# Adafruit-Feather.net
KiCad netlist of a schematic drawn in EAGLE
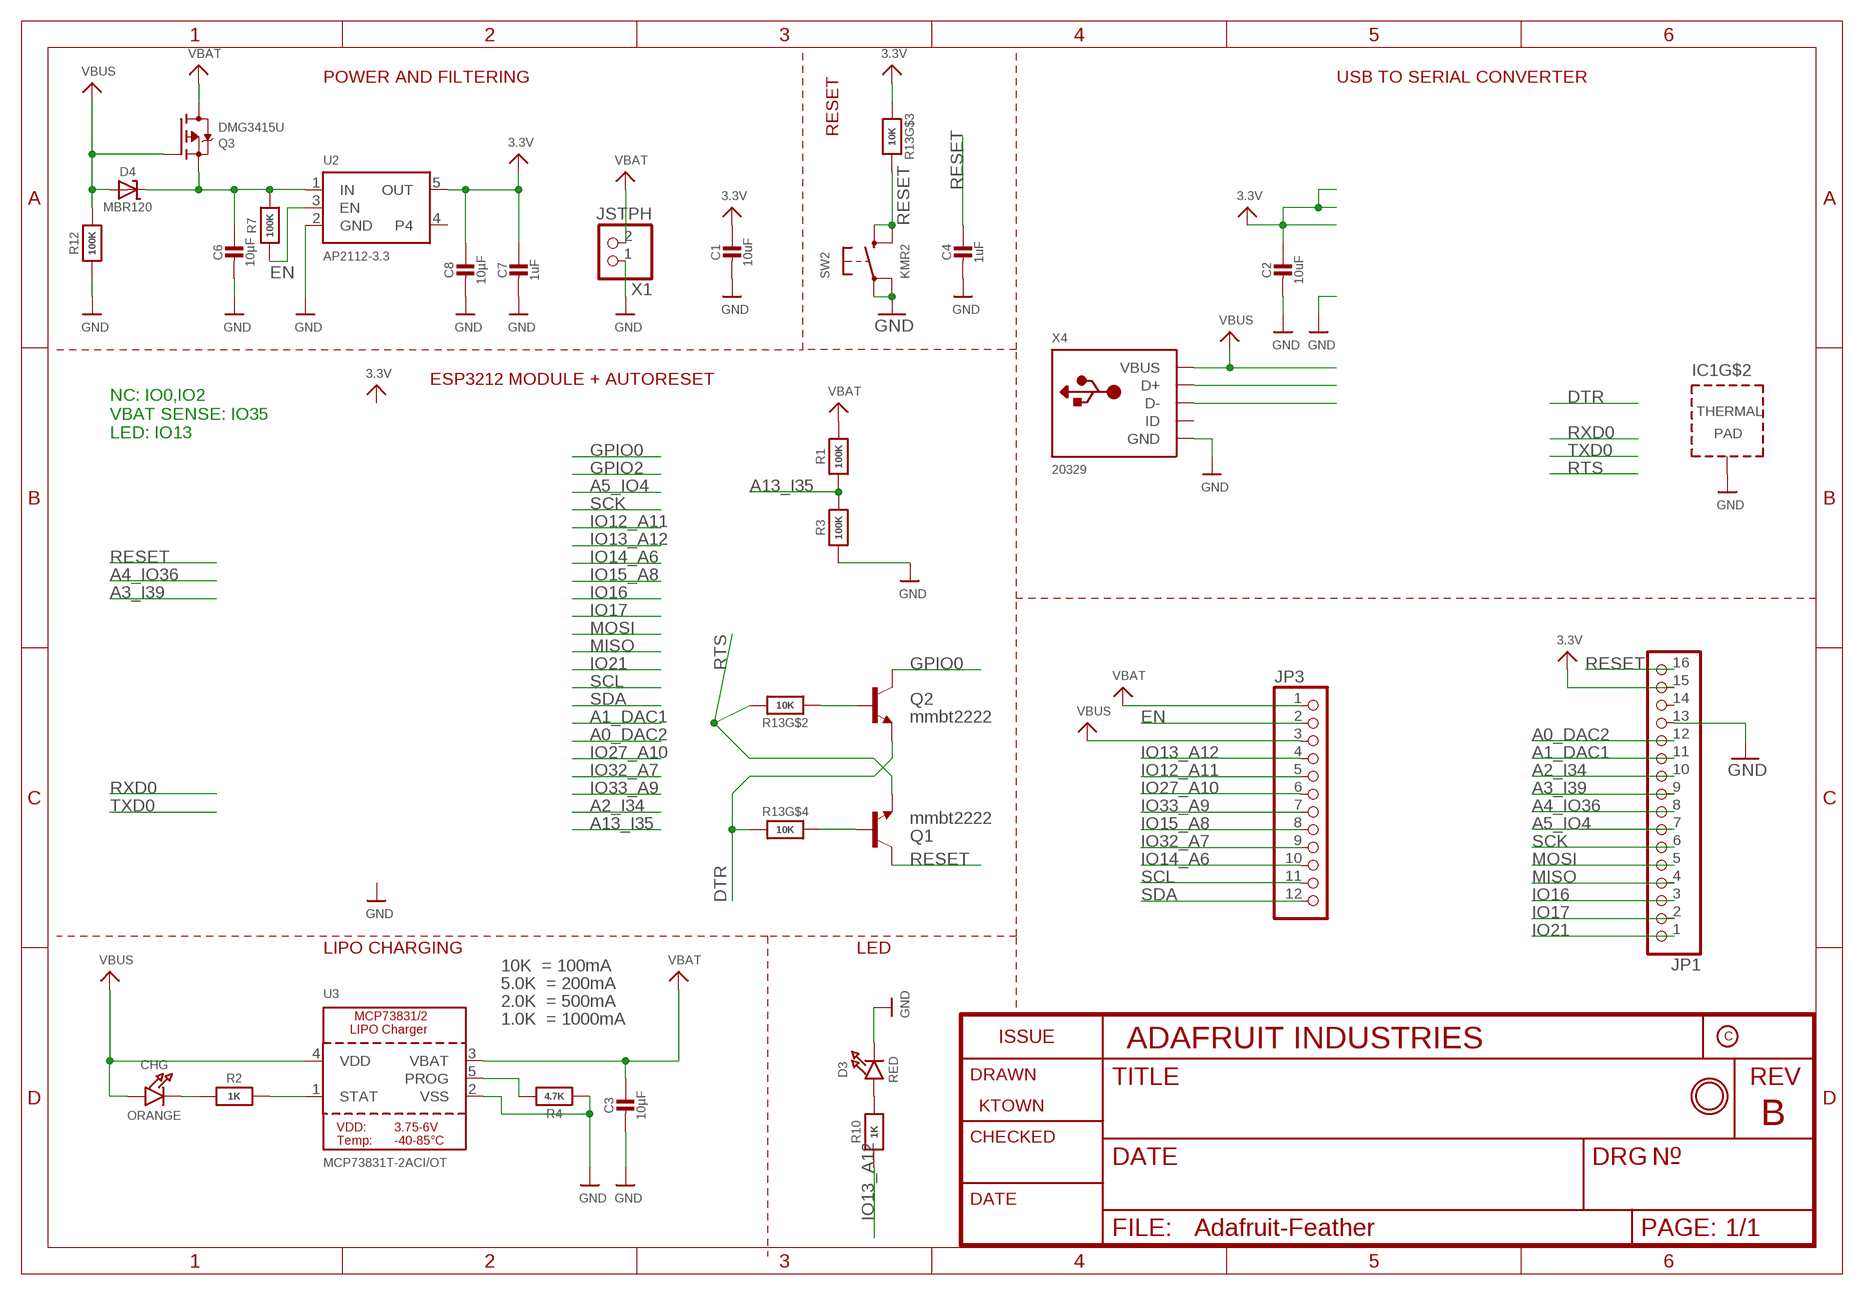
[diagram p0: schematic, sheet 1]

(export (version "E")
  (design (tool "Eeschema 10.0.6"))
  (components
    (comp (ref "C1")
      (value "10uF")
      (footprint "eagle-import:0805-NO")
      (libsource (lib "eagle-import") (part "CAP_CERAMIC0805-NOOUTLINE"))
    )
    (comp (ref "C2")
      (value "10uF")
      (footprint "eagle-import:0805-NO")
      (libsource (lib "eagle-import") (part "CAP_CERAMIC0805-NOOUTLINE"))
    )
    (comp (ref "C3")
      (value "10µF")
      (footprint "eagle-import:0805-NO")
      (libsource (lib "eagle-import") (part "CAP_CERAMIC0805-NOOUTLINE"))
    )
    (comp (ref "C4")
      (value "1uF")
      (footprint "eagle-import:0603-NO")
      (libsource (lib "eagle-import") (part "CAP_CERAMIC0603_NO"))
    )
    (comp (ref "C6")
      (value "10µF")
      (footprint "eagle-import:0805-NO")
      (libsource (lib "eagle-import") (part "CAP_CERAMIC0805-NOOUTLINE"))
    )
    (comp (ref "C7")
      (value "1uF")
      (footprint "eagle-import:0603-NO")
      (libsource (lib "eagle-import") (part "CAP_CERAMIC0603_NO"))
    )
    (comp (ref "C8")
      (value "10µF")
      (footprint "eagle-import:0805-NO")
      (libsource (lib "eagle-import") (part "CAP_CERAMIC0805-NOOUTLINE"))
    )
    (comp (ref "CHG")
      (value "ORANGE")
      (footprint "eagle-import:CHIPLED_0805_NOOUTLINE")
      (libsource (lib "eagle-import") (part "LED0805_NOOUTLINE"))
    )
    (comp (ref "D3")
      (value "RED")
      (footprint "eagle-import:CHIPLED_0805_NOOUTLINE")
      (libsource (lib "eagle-import") (part "LED0805_NOOUTLINE"))
    )
    (comp (ref "D4")
      (value "MBR120")
      (footprint "eagle-import:SOD-123")
      (libsource (lib "eagle-import") (part "DIODE-SCHOTTKYSOD-123"))
    )
    (comp (ref "IC1")
      (value "CP2104")
      (footprint "eagle-import:QFN24_4MM_SMSC")
      (libsource (lib "eagle-import") (part "CP2104"))
    )
    (comp (ref "JP1")
      (value "HEADER-1X16_MIN")
      (footprint "eagle-import:1X16_ROUND_MIN")
      (libsource (lib "eagle-import") (part "HEADER-1X16_MIN"))
    )
    (comp (ref "JP3")
      (value "HEADER-1X12_MIN")
      (footprint "eagle-import:1X12_ROUND_MIN")
      (libsource (lib "eagle-import") (part "HEADER-1X12_MIN"))
    )
    (comp (ref "Q1")
      (value "mmbt2222")
      (footprint "eagle-import:SOT23-3")
      (libsource (lib "eagle-import") (part "TRANSISTOR_NPNSOT23-3"))
    )
    (comp (ref "Q2")
      (value "mmbt2222")
      (footprint "eagle-import:SOT23-3")
      (libsource (lib "eagle-import") (part "TRANSISTOR_NPNSOT23-3"))
    )
    (comp (ref "Q3")
      (value "DMG3415U")
      (footprint "eagle-import:SOT23-R")
      (libsource (lib "eagle-import") (part "MOSFET-P"))
    )
    (comp (ref "R1")
      (value "100K")
      (footprint "eagle-import:0603-NO")
      (libsource (lib "eagle-import") (part "RESISTOR_0603_NOOUT"))
    )
    (comp (ref "R2")
      (value "1K")
      (footprint "eagle-import:0603-NO")
      (libsource (lib "eagle-import") (part "RESISTOR_0603_NOOUT"))
    )
    (comp (ref "R3")
      (value "100K")
      (footprint "eagle-import:0603-NO")
      (libsource (lib "eagle-import") (part "RESISTOR_0603_NOOUT"))
    )
    (comp (ref "R4")
      (value "4.7K")
      (footprint "eagle-import:0603-NO")
      (libsource (lib "eagle-import") (part "RESISTOR_0603_NOOUT"))
    )
    (comp (ref "R7")
      (value "100K")
      (footprint "eagle-import:0603-NO")
      (libsource (lib "eagle-import") (part "RESISTOR_0603_NOOUT"))
    )
    (comp (ref "R10")
      (value "1K")
      (footprint "eagle-import:0603-NO")
      (libsource (lib "eagle-import") (part "RESISTOR_0603_NOOUT"))
    )
    (comp (ref "R12")
      (value "100K")
      (footprint "eagle-import:0603-NO")
      (libsource (lib "eagle-import") (part "RESISTOR_0603_NOOUT"))
    )
    (comp (ref "R13")
      (value "10K")
      (footprint "eagle-import:RESPACK_4X0603")
      (libsource (lib "eagle-import") (part "RESISTOR_4PACK"))
    )
    (comp (ref "SW2")
      (value "KMR2")
      (footprint "eagle-import:BTN_KMR2_4.6X2.8")
      (libsource (lib "eagle-import") (part "SWITCH_TACT_SMT4.6X2.8"))
    )
    (comp (ref "U$32")
      (value "MOUNTINGHOLE2.5")
      (footprint "eagle-import:MOUNTINGHOLE_2.5_PLATED")
      (libsource (lib "eagle-import") (part "MOUNTINGHOLE2.5"))
    )
    (comp (ref "U2")
      (value "AP2112-3.3")
      (footprint "eagle-import:SOT23-5")
      (libsource (lib "eagle-import") (part "VREG_SOT23-5"))
    )
    (comp (ref "U3")
      (value "MCP73831T-2ACI/OT")
      (footprint "eagle-import:SOT23-5")
      (libsource (lib "eagle-import") (part "MCP73831/2"))
    )
    (comp (ref "X1")
      (value "JSTPH")
      (footprint "eagle-import:JSTPH2")
      (libsource (lib "eagle-import") (part "CON_JST_PH_2PIN"))
    )
    (comp (ref "X4")
      (value "20329")
      (footprint "eagle-import:4UCONN_20329_V2")
      (libsource (lib "eagle-import") (part "USB_MICRO_20329_V2"))
    )
  )
  (nets
    (net (code "1") (name "/A0_DAC2") (class "Default")
      (node (ref "JP1") (pin "12") (pinfunction "12_12") (pintype "passive"))
    )
    (net (code "2") (name "/A1_DAC1") (class "Default")
      (node (ref "JP1") (pin "11") (pinfunction "11_11") (pintype "passive"))
    )
    (net (code "3") (name "/A2_I34") (class "Default")
      (node (ref "JP1") (pin "10") (pinfunction "10_10") (pintype "passive"))
    )
    (net (code "4") (name "/A3_I39") (class "Default")
      (node (ref "JP1") (pin "9") (pinfunction "9_9") (pintype "passive"))
    )
    (net (code "5") (name "/A4_IO36") (class "Default")
      (node (ref "JP1") (pin "8") (pinfunction "8_8") (pintype "passive"))
    )
    (net (code "6") (name "/A5_IO4") (class "Default")
      (node (ref "JP1") (pin "7") (pinfunction "7_7") (pintype "passive"))
    )
    (net (code "7") (name "/A13_I35") (class "Default")
      (node (ref "R1") (pin "1") (pinfunction "1_1") (pintype "passive"))
      (node (ref "R3") (pin "2") (pinfunction "2_2") (pintype "passive"))
    )
    (net (code "8") (name "/DTR") (class "Default")
      (node (ref "Q2") (pin "2") (pinfunction "E_2") (pintype "passive"))
      (node (ref "R13") (pin "4") (pinfunction "1_4") (pintype "passive"))
    )
    (net (code "9") (name "/EN") (class "Default")
      (node (ref "JP3") (pin "2") (pinfunction "2_2") (pintype "passive"))
      (node (ref "R7") (pin "1") (pinfunction "1_1") (pintype "passive"))
      (node (ref "U2") (pin "3") (pinfunction "EN_3") (pintype "input"))
    )
    (net (code "10") (name "/GPIO0") (class "Default")
      (node (ref "Q2") (pin "3") (pinfunction "C_3") (pintype "passive"))
    )
    (net (code "12") (name "/IO12_A11") (class "Default")
      (node (ref "JP3") (pin "5") (pinfunction "5_5") (pintype "passive"))
    )
    (net (code "13") (name "/IO13_A12") (class "Default")
      (node (ref "JP3") (pin "4") (pinfunction "4_4") (pintype "passive"))
      (node (ref "R10") (pin "1") (pinfunction "1_1") (pintype "passive"))
    )
    (net (code "14") (name "/IO14_A6") (class "Default")
      (node (ref "JP3") (pin "10") (pinfunction "10_10") (pintype "passive"))
    )
    (net (code "15") (name "/IO15_A8") (class "Default")
      (node (ref "JP3") (pin "8") (pinfunction "8_8") (pintype "passive"))
    )
    (net (code "16") (name "/IO16") (class "Default")
      (node (ref "JP1") (pin "3") (pinfunction "3_3") (pintype "passive"))
    )
    (net (code "17") (name "/IO17") (class "Default")
      (node (ref "JP1") (pin "2") (pinfunction "2_2") (pintype "passive"))
    )
    (net (code "18") (name "/IO21") (class "Default")
      (node (ref "JP1") (pin "1") (pinfunction "1_1") (pintype "passive"))
    )
    (net (code "19") (name "/IO27_A10") (class "Default")
      (node (ref "JP3") (pin "6") (pinfunction "6_6") (pintype "passive"))
    )
    (net (code "20") (name "/IO32_A7") (class "Default")
      (node (ref "JP3") (pin "9") (pinfunction "9_9") (pintype "passive"))
    )
    (net (code "21") (name "/IO33_A9") (class "Default")
      (node (ref "JP3") (pin "7") (pinfunction "7_7") (pintype "passive"))
    )
    (net (code "22") (name "/MISO") (class "Default")
      (node (ref "JP1") (pin "4") (pinfunction "4_4") (pintype "passive"))
    )
    (net (code "23") (name "/MOSI") (class "Default")
      (node (ref "JP1") (pin "5") (pinfunction "5_5") (pintype "passive"))
    )
    (net (code "24") (name "/RESET") (class "Default")
      (node (ref "C4") (pin "1") (pinfunction "1_1") (pintype "passive"))
      (node (ref "JP1") (pin "16") (pinfunction "16_16") (pintype "passive"))
      (node (ref "Q1") (pin "3") (pinfunction "C_3") (pintype "passive"))
      (node (ref "R13") (pin "6") (pinfunction "2_6") (pintype "passive"))
      (node (ref "SW2") (pin "B") (pinfunction "S_B") (pintype "passive"))
      (node (ref "SW2") (pin "B'") (pinfunction "S1_B'") (pintype "passive"))
    )
    (net (code "25") (name "/RTS") (class "Default")
      (node (ref "Q1") (pin "2") (pinfunction "E_2") (pintype "passive"))
      (node (ref "R13") (pin "7") (pinfunction "2_7") (pintype "passive"))
    )
    (net (code "27") (name "/SCK") (class "Default")
      (node (ref "JP1") (pin "6") (pinfunction "6_6") (pintype "passive"))
    )
    (net (code "28") (name "/SCL") (class "Default")
      (node (ref "JP3") (pin "11") (pinfunction "11_11") (pintype "passive"))
    )
    (net (code "29") (name "/SDA") (class "Default")
      (node (ref "JP3") (pin "12") (pinfunction "12_12") (pintype "passive"))
    )
    (net (code "31") (name "3.3V") (class "Default")
      (node (ref "C1") (pin "1") (pinfunction "1_1") (pintype "passive"))
      (node (ref "C2") (pin "1") (pinfunction "1_1") (pintype "passive"))
      (node (ref "C7") (pin "1") (pinfunction "1_1") (pintype "passive"))
      (node (ref "C8") (pin "1") (pinfunction "1_1") (pintype "passive"))
      (node (ref "JP1") (pin "15") (pinfunction "15_15") (pintype "passive"))
      (node (ref "R13") (pin "3") (pinfunction "1_3") (pintype "passive"))
      (node (ref "U2") (pin "5") (pinfunction "OUT_5") (pintype "power_in"))
    )
    (net (code "32") (name "GND") (class "Default")
      (node (ref "C1") (pin "2") (pinfunction "2_2") (pintype "passive"))
      (node (ref "C2") (pin "2") (pinfunction "2_2") (pintype "passive"))
      (node (ref "C3") (pin "2") (pinfunction "2_2") (pintype "passive"))
      (node (ref "C4") (pin "2") (pinfunction "2_2") (pintype "passive"))
      (node (ref "C6") (pin "2") (pinfunction "2_2") (pintype "passive"))
      (node (ref "C7") (pin "2") (pinfunction "2_2") (pintype "passive"))
      (node (ref "C8") (pin "2") (pinfunction "2_2") (pintype "passive"))
      (node (ref "D3") (pin "C") (pinfunction "C_C") (pintype "passive"))
      (node (ref "IC1") (pin "THERM") (pinfunction "TP_THERM") (pintype "power_in"))
      (node (ref "JP1") (pin "13") (pinfunction "13_13") (pintype "passive"))
      (node (ref "R12") (pin "1") (pinfunction "1_1") (pintype "passive"))
      (node (ref "R3") (pin "1") (pinfunction "1_1") (pintype "passive"))
      (node (ref "R4") (pin "1") (pinfunction "1_1") (pintype "passive"))
      (node (ref "SW2") (pin "A") (pinfunction "P_A") (pintype "passive"))
      (node (ref "SW2") (pin "A'") (pinfunction "P1_A'") (pintype "passive"))
      (node (ref "U2") (pin "2") (pinfunction "GND_2") (pintype "power_in"))
      (node (ref "U3") (pin "2") (pinfunction "VSS_2") (pintype "power_in"))
      (node (ref "X1") (pin "1") (pinfunction "1_1") (pintype "passive"))
      (node (ref "X4") (pin "BASE@1") (pinfunction "GND_BASE@1") (pintype "power_in"))
      (node (ref "X4") (pin "BASE@2") (pinfunction "GND_BASE@2") (pintype "power_in"))
      (node (ref "X4") (pin "GND") (pinfunction "GND_GND") (pintype "power_in"))
      (node (ref "X4") (pin "SPRT@1") (pinfunction "GND_SPRT@1") (pintype "power_in"))
      (node (ref "X4") (pin "SPRT@2") (pinfunction "GND_SPRT@2") (pintype "power_in"))
      (node (ref "X4") (pin "SPRT@3") (pinfunction "GND_SPRT@3") (pintype "power_in"))
      (node (ref "X4") (pin "SPRT@4") (pinfunction "GND_SPRT@4") (pintype "power_in"))
    )
    (net (code "33") (name "Net-(CHG-PadC)") (class "Default")
      (node (ref "CHG") (pin "C") (pinfunction "C_C") (pintype "passive"))
      (node (ref "R2") (pin "1") (pinfunction "1_1") (pintype "passive"))
    )
    (net (code "34") (name "Net-(D3-PadA)") (class "Default")
      (node (ref "D3") (pin "A") (pinfunction "A_A") (pintype "passive"))
      (node (ref "R10") (pin "2") (pinfunction "2_2") (pintype "passive"))
    )
    (net (code "35") (name "Net-(Q1-B)") (class "Default")
      (node (ref "Q1") (pin "1") (pinfunction "B_1") (pintype "passive"))
      (node (ref "R13") (pin "5") (pinfunction "2_5") (pintype "passive"))
    )
    (net (code "36") (name "Net-(Q2-B)") (class "Default")
      (node (ref "Q2") (pin "1") (pinfunction "B_1") (pintype "passive"))
      (node (ref "R13") (pin "2") (pinfunction "1_2") (pintype "passive"))
    )
    (net (code "37") (name "Net-(Q3-S)") (class "Default")
      (node (ref "C6") (pin "1") (pinfunction "1_1") (pintype "passive"))
      (node (ref "D4") (pin "C") (pinfunction "C_C") (pintype "passive"))
      (node (ref "Q3") (pin "2") (pinfunction "S_2") (pintype "passive"))
      (node (ref "R7") (pin "2") (pinfunction "2_2") (pintype "passive"))
      (node (ref "U2") (pin "1") (pinfunction "IN_1") (pintype "power_in"))
    )
    (net (code "38") (name "Net-(U3-PROG)") (class "Default")
      (node (ref "R4") (pin "2") (pinfunction "2_2") (pintype "passive"))
      (node (ref "U3") (pin "5") (pinfunction "PROG_5") (pintype "input"))
    )
    (net (code "39") (name "Net-(U3-STAT)") (class "Default")
      (node (ref "R2") (pin "2") (pinfunction "2_2") (pintype "passive"))
      (node (ref "U3") (pin "1") (pinfunction "STAT_1") (pintype "output"))
    )
    (net (code "40") (name "VBAT") (class "Default")
      (node (ref "C3") (pin "1") (pinfunction "1_1") (pintype "passive"))
      (node (ref "JP3") (pin "1") (pinfunction "1_1") (pintype "passive"))
      (node (ref "Q3") (pin "3") (pinfunction "D_3") (pintype "passive"))
      (node (ref "R1") (pin "2") (pinfunction "2_2") (pintype "passive"))
      (node (ref "U3") (pin "3") (pinfunction "VBAT_3") (pintype "power_in"))
      (node (ref "X1") (pin "2") (pinfunction "2_2") (pintype "passive"))
    )
    (net (code "41") (name "VBUS") (class "Default")
      (node (ref "CHG") (pin "A") (pinfunction "A_A") (pintype "passive"))
      (node (ref "D4") (pin "A") (pinfunction "A_A") (pintype "passive"))
      (node (ref "JP3") (pin "3") (pinfunction "3_3") (pintype "passive"))
      (node (ref "Q3") (pin "1") (pinfunction "G_1") (pintype "passive"))
      (node (ref "R12") (pin "2") (pinfunction "2_2") (pintype "passive"))
      (node (ref "U3") (pin "4") (pinfunction "VDD_4") (pintype "power_in"))
      (node (ref "X4") (pin "VBUS") (pinfunction "VBUS_VBUS") (pintype "power_in"))
    )
    (net (code "42") (name "unconnected-(JP1-Pad14)") (class "Default")
      (node (ref "JP1") (pin "14") (pinfunction "14_14") (pintype "passive"))
    )
    (net (code "43") (name "unconnected-(U2-P4-Pad4)") (class "Default")
      (node (ref "U2") (pin "4") (pinfunction "P4_4") (pintype "bidirectional"))
    )
    (net (code "44") (name "unconnected-(X4-PadD+)") (class "Default")
      (node (ref "X4") (pin "D+") (pinfunction "D+_D+") (pintype "bidirectional"))
    )
    (net (code "45") (name "unconnected-(X4-PadD-)") (class "Default")
      (node (ref "X4") (pin "D-") (pinfunction "D-_D-") (pintype "bidirectional"))
    )
    (net (code "46") (name "unconnected-(X4-PadID)") (class "Default")
      (node (ref "X4") (pin "ID") (pinfunction "ID_ID") (pintype "bidirectional"))
    )
  )
)
